# SC_generator.net
KiCad netlist of a schematic drawn in Altium Designer
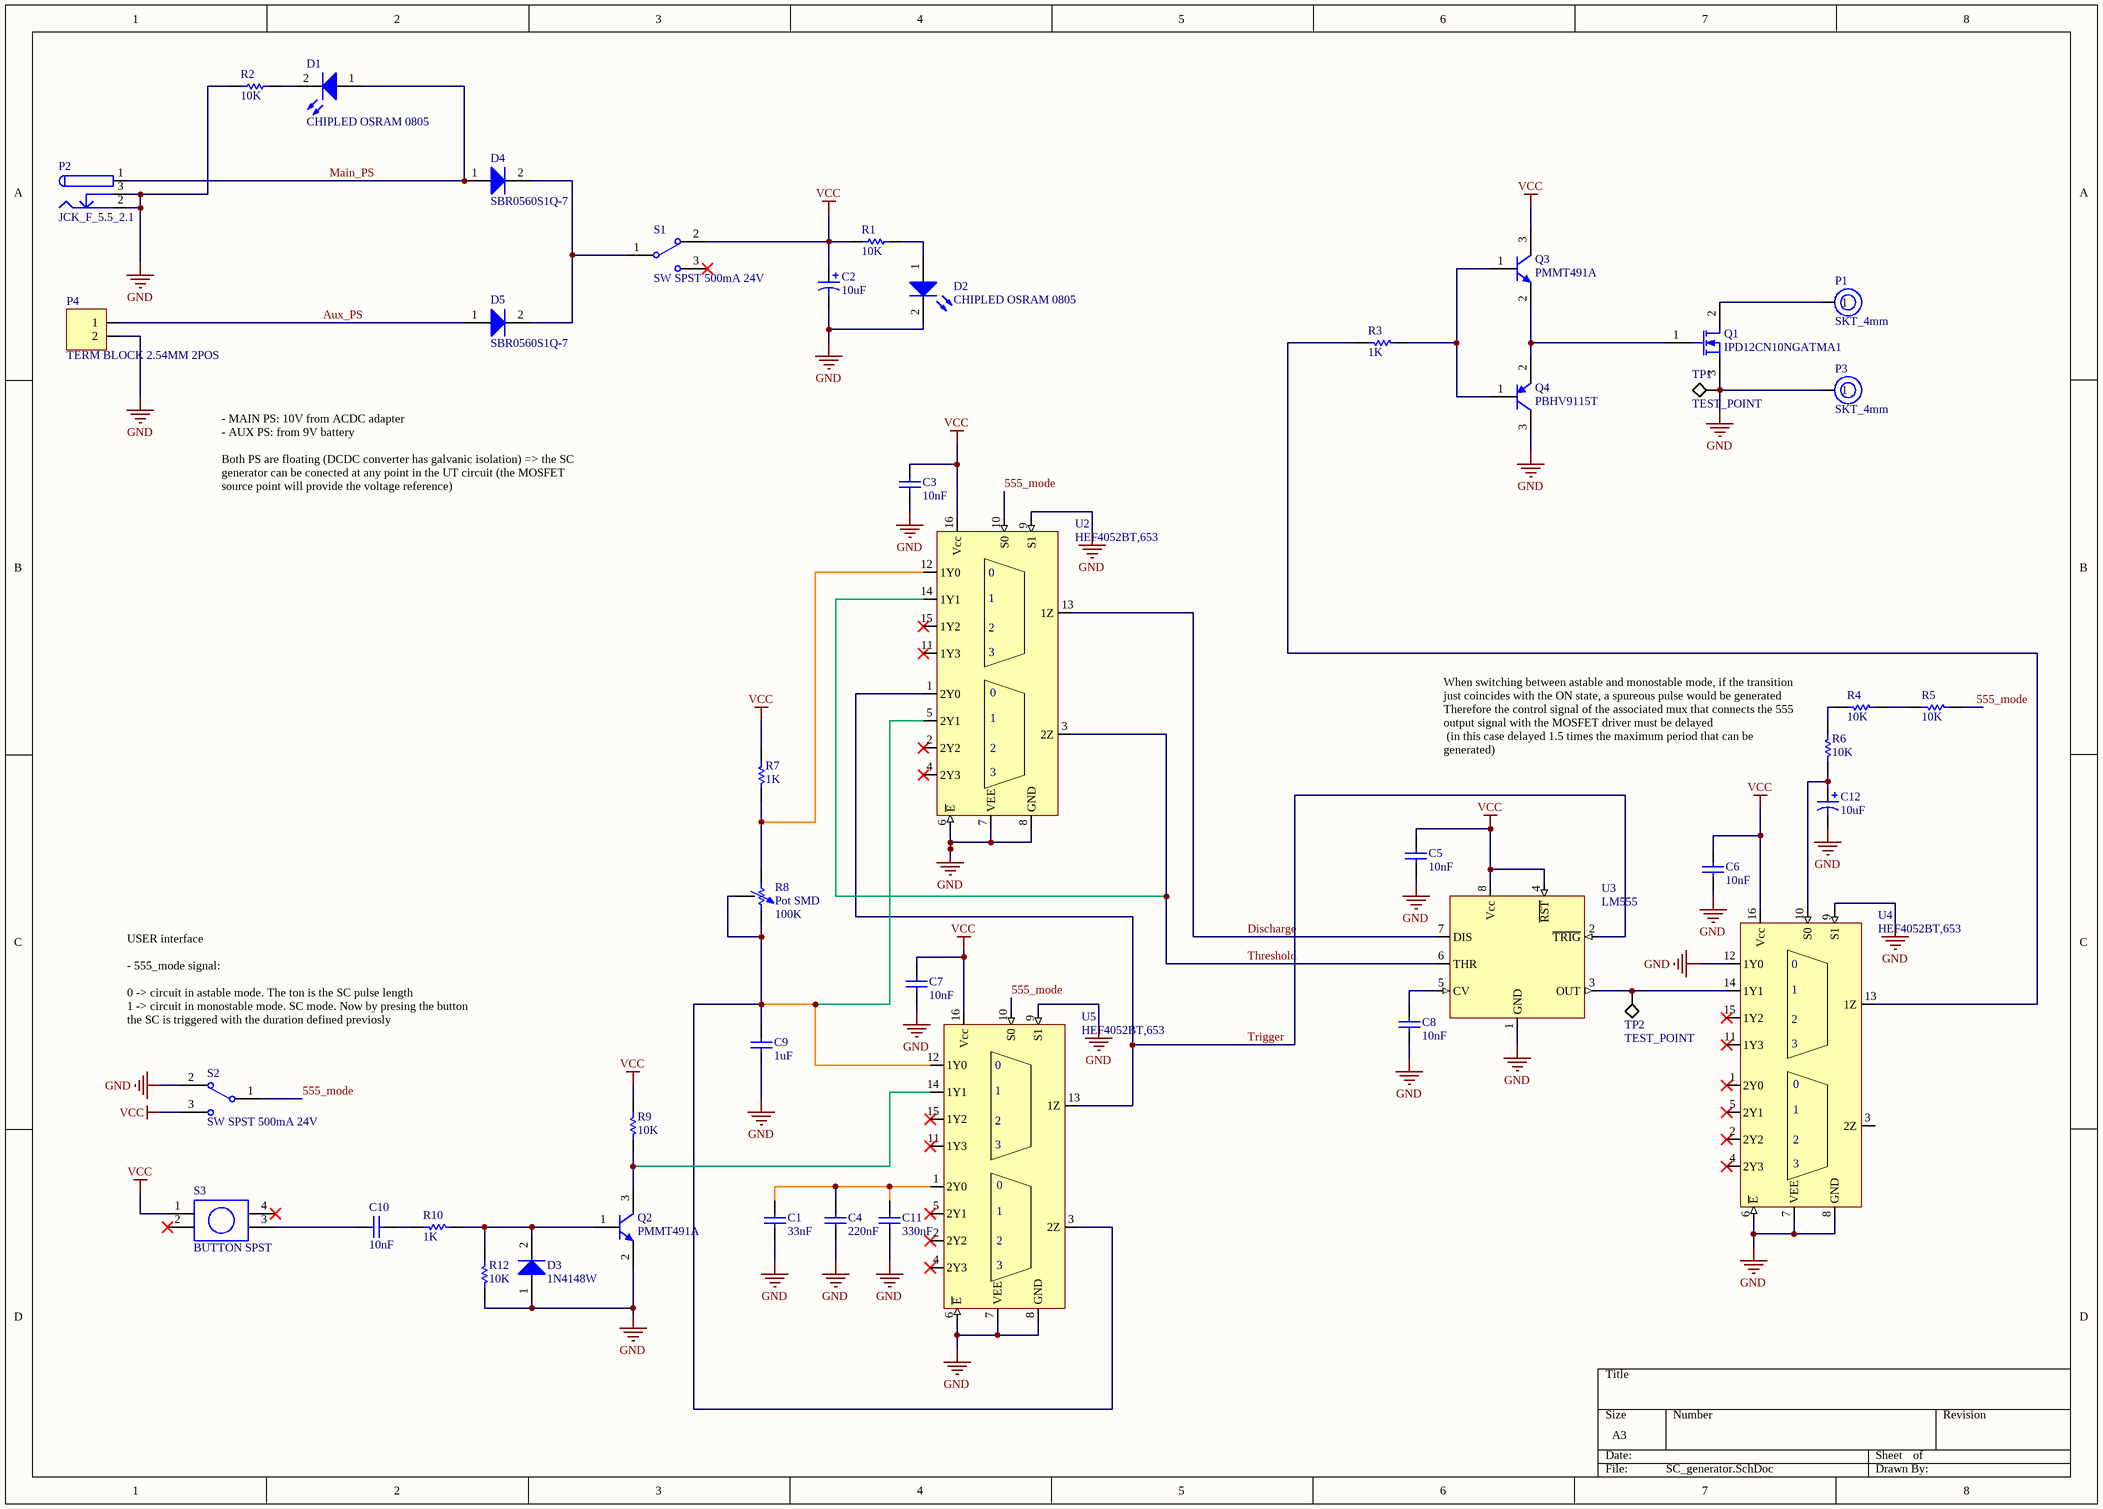
[diagram p0: SC_generator.SchDoc]

(export (version "E")
  (design (tool "Eeschema 10.0.6"))
  (components
    (comp (ref "C1")
      (value "33nF")
      (footprint "CAP_0805_L")
      (description "Generic ceramic capacitor")
      (fields (field (name "Comment") "Cap Semi"))
      (libsource (lib "PAM_capacitors") (part "Cap Semi"))
    )
    (comp (ref "C2")
      (value "10uF")
      (footprint "CAPAE5043X55M")
      (description "Generic electrolitic capacitor")
      (fields (field (name "Comment") "Cap Electrol"))
      (libsource (lib "PAM_capacitors") (part "Cap Electrol"))
    )
    (comp (ref "C3")
      (value "10nF")
      (footprint "CAP_0805_L")
      (description "Generic ceramic capacitor")
      (fields (field (name "Comment") "Cap Semi"))
      (libsource (lib "PAM_capacitors") (part "Cap Semi"))
    )
    (comp (ref "C4")
      (value "220nF")
      (footprint "CAP_0805_L")
      (description "Generic ceramic capacitor")
      (fields (field (name "Comment") "Cap Semi"))
      (libsource (lib "PAM_capacitors") (part "Cap Semi"))
    )
    (comp (ref "C5")
      (value "10nF")
      (footprint "CAP_0805_L")
      (description "Generic ceramic capacitor")
      (fields (field (name "Comment") "Cap Semi"))
      (libsource (lib "PAM_capacitors") (part "Cap Semi"))
    )
    (comp (ref "C6")
      (value "10nF")
      (footprint "CAP_0805_L")
      (description "Generic ceramic capacitor")
      (fields (field (name "Comment") "Cap Semi"))
      (libsource (lib "PAM_capacitors") (part "Cap Semi"))
    )
    (comp (ref "C7")
      (value "10nF")
      (footprint "CAP_0805_L")
      (description "Generic ceramic capacitor")
      (fields (field (name "Comment") "Cap Semi"))
      (libsource (lib "PAM_capacitors") (part "Cap Semi"))
    )
    (comp (ref "C8")
      (value "10nF")
      (footprint "CAP_0805_L")
      (description "Generic ceramic capacitor")
      (fields (field (name "Comment") "Cap Semi"))
      (libsource (lib "PAM_capacitors") (part "Cap Semi"))
    )
    (comp (ref "C9")
      (value "1uF")
      (footprint "CAP_0805_L")
      (description "Generic ceramic capacitor")
      (fields (field (name "Comment") "Cap Semi"))
      (libsource (lib "PAM_capacitors") (part "Cap Semi"))
    )
    (comp (ref "C10")
      (value "10nF")
      (footprint "CAP_0805_L")
      (description "Generic ceramic capacitor")
      (fields (field (name "Comment") "Cap Semi"))
      (libsource (lib "PAM_capacitors") (part "Cap Semi"))
    )
    (comp (ref "C11")
      (value "330nF")
      (footprint "CAP_0805_L")
      (description "Generic ceramic capacitor")
      (fields (field (name "Comment") "Cap Semi"))
      (libsource (lib "PAM_capacitors") (part "Cap Semi"))
    )
    (comp (ref "C12")
      (value "10uF")
      (footprint "CAPAE5043X55M")
      (description "Generic electrolitic capacitor")
      (fields (field (name "Comment") "Cap Electrol"))
      (libsource (lib "PAM_capacitors") (part "Cap Electrol"))
    )
    (comp (ref "D1")
      (value "CHIPLED OSRAM 0805")
      (footprint "CHIPLED_0805_N")
      (libsource (lib "PAM_diodes") (part "CHIPLED 0805"))
    )
    (comp (ref "D2")
      (value "CHIPLED OSRAM 0805")
      (footprint "CHIPLED_0805_N")
      (libsource (lib "PAM_diodes") (part "CHIPLED 0805"))
    )
    (comp (ref "D3")
      (value "1N4148W")
      (footprint "SOD-123_M")
      (description "Diodo de conmutación, 1N4148W-E3-08, 150mA, 75V, SOD-123, 2-Pines, Maximum of 50")
      (libsource (lib "PAM_diodes") (part "1N4148W"))
    )
    (comp (ref "D4")
      (value "SBR0560S1Q-7")
      (footprint "SOD-123_M")
      (description "Diodo Súper barrera Montaje en superficie 60V 500 mA SOD-123")
      (libsource (lib "PAM_diodes") (part "SBR0560S1Q-7"))
    )
    (comp (ref "D5")
      (value "SBR0560S1Q-7")
      (footprint "SOD-123_M")
      (description "Diodo Súper barrera Montaje en superficie 60V 500 mA SOD-123")
      (libsource (lib "PAM_diodes") (part "SBR0560S1Q-7"))
    )
    (comp (ref "P1")
      (value "SKT_4mm")
      (footprint "4MM SAFETY JACK")
      (libsource (lib "PAM_connectors") (part "SKT_4mm"))
    )
    (comp (ref "P2")
      (value "JCK_F_5.5_2.1")
      (footprint "PJ-059A")
      (description "Power Barrel Connector Jack 2.10mm ID (0.083\"), 5.50mm OD (0.217\") Through Hole, Right Angle")
      (libsource (lib "PAM_connectors") (part "jack_female_5.5_2.1"))
    )
    (comp (ref "P3")
      (value "SKT_4mm")
      (footprint "4MM SAFETY JACK")
      (libsource (lib "PAM_connectors") (part "SKT_4mm"))
    )
    (comp (ref "P4")
      (value "TERM BLOCK 2.54MM 2POS")
      (footprint "TERM BLOCK 2.54MM 2POS")
      (description "2 Position Wire to Board Terminal Block Horizontal with Board 0.100\" (2.54mm) Through Hole")
      (libsource (lib "PAM_connectors") (part "TERM BLOCK 2.54MM 2POS"))
    )
    (comp (ref "Q1")
      (value "IPD12CN10NGATMA1")
      (footprint "TO-252/DPAK")
      (description "Canal N Montaje en superficie 100V 67 A (Tc) 125 W (Tc) PG-TO252-3")
      (libsource (lib "PAM_Transistors") (part "IPD12CN10NGATMA1"))
    )
    (comp (ref "Q2")
      (value "PMMT491A")
      (footprint "SOT-23")
      (description "Transistor de Unión Bipolar Único, NPN, 40 V, 250 mW, 1 A, 300 hFE")
      (libsource (lib "PAM_Transistors") (part "PMMT491A"))
    )
    (comp (ref "Q3")
      (value "PMMT491A")
      (footprint "SOT-23")
      (description "Transistor de Unión Bipolar Único, NPN, 40 V, 250 mW, 1 A, 300 hFE")
      (libsource (lib "PAM_Transistors") (part "PMMT491A"))
    )
    (comp (ref "Q4")
      (value "PBHV9115T")
      (footprint "SOT-23")
      (description "Transistor de Unión Bipolar Único, PNP, -150 V, 115 MHz, 300 mW, -1 A, 220 hFE")
      (libsource (lib "PAM_Transistors") (part "PBHV9115T"))
    )
    (comp (ref "R1")
      (value "10K")
      (footprint "RES_1206_N")
      (description "Generic resistor")
      (fields (field (name "Comment") "Res semi"))
      (libsource (lib "PAM_resistors") (part "Res semi"))
    )
    (comp (ref "R2")
      (value "10K")
      (footprint "RES_1206_N")
      (description "Generic resistor")
      (fields (field (name "Comment") "Res semi"))
      (libsource (lib "PAM_resistors") (part "Res semi"))
    )
    (comp (ref "R3")
      (value "1K")
      (footprint "RES_1206_N")
      (description "Generic resistor")
      (fields (field (name "Comment") "Res semi"))
      (libsource (lib "PAM_resistors") (part "Res semi"))
    )
    (comp (ref "R4")
      (value "10K")
      (footprint "RES_1206_N")
      (description "Generic resistor")
      (fields (field (name "Comment") "Res semi"))
      (libsource (lib "PAM_resistors") (part "Res semi"))
    )
    (comp (ref "R5")
      (value "10K")
      (footprint "RES_1206_N")
      (description "Generic resistor")
      (fields (field (name "Comment") "Res semi"))
      (libsource (lib "PAM_resistors") (part "Res semi"))
    )
    (comp (ref "R6")
      (value "10K")
      (footprint "RES_1206_N")
      (description "Generic resistor")
      (fields (field (name "Comment") "Res semi"))
      (libsource (lib "PAM_resistors") (part "Res semi"))
    )
    (comp (ref "R7")
      (value "1K")
      (footprint "RES_1206_N")
      (description "Generic resistor")
      (fields (field (name "Comment") "Res semi"))
      (libsource (lib "PAM_resistors") (part "Res semi"))
    )
    (comp (ref "R8")
      (value "Pot SMD")
      (footprint "3361P_POT")
      (description "Generic pot SMD")
      (fields (field (name "ALTIUM_VALUE") "100K"))
      (libsource (lib "PAM_resistors") (part "Pot SMD"))
    )
    (comp (ref "R9")
      (value "10K")
      (footprint "RES_1206_N")
      (description "Generic resistor")
      (fields (field (name "Comment") "Res semi"))
      (libsource (lib "PAM_resistors") (part "Res semi"))
    )
    (comp (ref "R10")
      (value "1K")
      (footprint "RES_1206_N")
      (description "Generic resistor")
      (fields (field (name "Comment") "Res semi"))
      (libsource (lib "PAM_resistors") (part "Res semi"))
    )
    (comp (ref "R12")
      (value "10K")
      (footprint "RES_1206_N")
      (description "Generic resistor")
      (fields (field (name "Comment") "Res semi"))
      (libsource (lib "PAM_resistors") (part "Res semi"))
    )
    (comp (ref "S1")
      (value "SW SPST 500mA 24V")
      (footprint "DIP_3x1_slide_switch")
      (description "Interruptor SIP, SPST, Pasante, Actuador Deslizante, 500 mA a 24 V")
      (libsource (lib "PAM_switches_buttons") (part "SW SPST TH"))
    )
    (comp (ref "S2")
      (value "SW SPST 500mA 24V")
      (footprint "DIP_3x1_slide_switch")
      (description "Interruptor SIP, SPST, Pasante, Actuador Deslizante, 500 mA a 24 V")
      (libsource (lib "PAM_switches_buttons") (part "SW SPST TH"))
    )
    (comp (ref "S3")
      (value "BUTTON SPST")
      (footprint "BUTTON SPDT")
      (description "Interruptor táctil tipo Botón, Negro, contactos SPST-NA, Montaje superficial")
      (libsource (lib "PAM_switches_buttons") (part "BUTTON SPST"))
    )
    (comp (ref "TP1")
      (value "TEST_POINT")
      (footprint "TP_SMD_pin")
      (description "Generic test point, several footprints")
      (libsource (lib "PAM_connectors") (part "TEST_POINT"))
    )
    (comp (ref "TP2")
      (value "TEST_POINT")
      (footprint "TP_SMD")
      (description "Generic test point, several footprints")
      (libsource (lib "PAM_connectors") (part "TEST_POINT"))
    )
    (comp (ref "U2")
      (value "HEF4052BT,653")
      (footprint "SO16_M")
      (description "IC MUX/DEMUX DUAL 4X1 16SOIC")
      (fields (field (name "MFR") "Nexperia"))
      (libsource (lib "PAM_ICs") (part "HEF4052BT,653"))
    )
    (comp (ref "U3")
      (value "LM555")
      (footprint "SO-8_M")
      (description "IC OSC SINGLE TIMER")
      (libsource (lib "PAM_ICs") (part "LM555"))
    )
    (comp (ref "U4")
      (value "HEF4052BT,653")
      (footprint "SO16_M")
      (description "IC MUX/DEMUX DUAL 4X1 16SOIC")
      (fields (field (name "MFR") "Nexperia"))
      (libsource (lib "PAM_ICs") (part "HEF4052BT,653"))
    )
    (comp (ref "U5")
      (value "HEF4052BT,653")
      (footprint "SO16_M")
      (description "IC MUX/DEMUX DUAL 4X1 16SOIC")
      (fields (field (name "MFR") "Nexperia"))
      (libsource (lib "PAM_ICs") (part "HEF4052BT,653"))
    )
  )
  (nets
    (net (code "1") (name "/555_mode") (class "Default")
      (node (ref "R5") (pin "1") (pinfunction "1_1") (pintype "passive"))
      (node (ref "S2") (pin "1") (pinfunction "C_1") (pintype "passive"))
      (node (ref "U2") (pin "10") (pinfunction "S0_10") (pintype "input"))
      (node (ref "U5") (pin "10") (pinfunction "S0_10") (pintype "input"))
    )
    (net (code "2") (name "/Aux_PS") (class "Default")
      (node (ref "D5") (pin "1") (pinfunction "A_1") (pintype "passive"))
      (node (ref "P4") (pin "1") (pinfunction "1_1") (pintype "passive"))
    )
    (net (code "3") (name "/Discharge") (class "Default")
      (node (ref "U2") (pin "13") (pinfunction "1Z_13") (pintype "bidirectional"))
      (node (ref "U3") (pin "7") (pinfunction "DIS_7") (pintype "passive"))
    )
    (net (code "4") (name "/Main_PS") (class "Default")
      (node (ref "D1") (pin "1") (pinfunction "A_1") (pintype "passive"))
      (node (ref "D4") (pin "1") (pinfunction "A_1") (pintype "passive"))
      (node (ref "P2") (pin "1") (pinfunction "tip_1") (pintype "power_in"))
    )
    (net (code "5") (name "/Threshold") (class "Default")
      (node (ref "U2") (pin "14") (pinfunction "1Y1_14") (pintype "bidirectional"))
      (node (ref "U2") (pin "3") (pinfunction "2Z_3") (pintype "bidirectional"))
      (node (ref "U3") (pin "6") (pinfunction "THR_6") (pintype "passive"))
    )
    (net (code "6") (name "/Trigger") (class "Default")
      (node (ref "U2") (pin "1") (pinfunction "2Y0_1") (pintype "bidirectional"))
      (node (ref "U3") (pin "2") (pinfunction "~{TRIG}_2") (pintype "input"))
      (node (ref "U5") (pin "13") (pinfunction "1Z_13") (pintype "bidirectional"))
    )
    (net (code "7") (name "GND") (class "Default")
      (node (ref "C1") (pin "1") (pinfunction "1_1") (pintype "passive"))
      (node (ref "C11") (pin "1") (pinfunction "1_1") (pintype "passive"))
      (node (ref "C12") (pin "2") (pinfunction "2_2") (pintype "passive"))
      (node (ref "C2") (pin "2") (pinfunction "2_2") (pintype "passive"))
      (node (ref "C3") (pin "1") (pinfunction "1_1") (pintype "passive"))
      (node (ref "C4") (pin "1") (pinfunction "1_1") (pintype "passive"))
      (node (ref "C5") (pin "1") (pinfunction "1_1") (pintype "passive"))
      (node (ref "C6") (pin "1") (pinfunction "1_1") (pintype "passive"))
      (node (ref "C7") (pin "1") (pinfunction "1_1") (pintype "passive"))
      (node (ref "C8") (pin "1") (pinfunction "1_1") (pintype "passive"))
      (node (ref "C9") (pin "1") (pinfunction "1_1") (pintype "passive"))
      (node (ref "D2") (pin "2") (pinfunction "K_2") (pintype "passive"))
      (node (ref "D3") (pin "1") (pinfunction "A_1") (pintype "passive"))
      (node (ref "P2") (pin "2") (pinfunction "sleeve_2") (pintype "power_in"))
      (node (ref "P2") (pin "3") (pinfunction "connector_detec_3") (pintype "power_in"))
      (node (ref "P3") (pin "1") (pinfunction "1_1") (pintype "passive"))
      (node (ref "P4") (pin "2") (pinfunction "2_2") (pintype "passive"))
      (node (ref "Q1") (pin "3") (pinfunction "S_3") (pintype "passive"))
      (node (ref "Q2") (pin "2") (pinfunction "E_2") (pintype "passive"))
      (node (ref "Q4") (pin "3") (pinfunction "C_3") (pintype "passive"))
      (node (ref "R12") (pin "1") (pinfunction "1_1") (pintype "passive"))
      (node (ref "R2") (pin "1") (pinfunction "1_1") (pintype "passive"))
      (node (ref "S2") (pin "2") (pinfunction "2_2") (pintype "passive"))
      (node (ref "TP1") (pin "1") (pinfunction "1_1") (pintype "passive"))
      (node (ref "U2") (pin "6") (pinfunction "~{E}_6") (pintype "input"))
      (node (ref "U2") (pin "7") (pinfunction "VEE_7") (pintype "power_in"))
      (node (ref "U2") (pin "8") (pinfunction "GND_8") (pintype "power_in"))
      (node (ref "U2") (pin "9") (pinfunction "S1_9") (pintype "input"))
      (node (ref "U3") (pin "1") (pinfunction "GND_1") (pintype "power_in"))
      (node (ref "U4") (pin "12") (pinfunction "1Y0_12") (pintype "bidirectional"))
      (node (ref "U4") (pin "6") (pinfunction "~{E}_6") (pintype "input"))
      (node (ref "U4") (pin "7") (pinfunction "VEE_7") (pintype "power_in"))
      (node (ref "U4") (pin "8") (pinfunction "GND_8") (pintype "power_in"))
      (node (ref "U4") (pin "9") (pinfunction "S1_9") (pintype "input"))
      (node (ref "U5") (pin "6") (pinfunction "~{E}_6") (pintype "input"))
      (node (ref "U5") (pin "7") (pinfunction "VEE_7") (pintype "power_in"))
      (node (ref "U5") (pin "8") (pinfunction "GND_8") (pintype "power_in"))
      (node (ref "U5") (pin "9") (pinfunction "S1_9") (pintype "input"))
    )
    (net (code "8") (name "Net-(C10-Pad2)") (class "Default")
      (node (ref "C10") (pin "2") (pinfunction "2_2") (pintype "passive"))
      (node (ref "R10") (pin "2") (pinfunction "2_2") (pintype "passive"))
    )
    (net (code "9") (name "Net-(D1-K)") (class "Default")
      (node (ref "D1") (pin "2") (pinfunction "K_2") (pintype "passive"))
      (node (ref "R2") (pin "2") (pinfunction "2_2") (pintype "passive"))
    )
    (net (code "10") (name "Net-(D2-A)") (class "Default")
      (node (ref "D2") (pin "1") (pinfunction "A_1") (pintype "passive"))
      (node (ref "R1") (pin "1") (pinfunction "1_1") (pintype "passive"))
    )
    (net (code "11") (name "Net-(D3-K)") (class "Default")
      (node (ref "D3") (pin "2") (pinfunction "K_2") (pintype "passive"))
      (node (ref "Q2") (pin "1") (pinfunction "B_1") (pintype "passive"))
      (node (ref "R10") (pin "1") (pinfunction "1_1") (pintype "passive"))
      (node (ref "R12") (pin "2") (pinfunction "2_2") (pintype "passive"))
    )
    (net (code "12") (name "Net-(D4-K)") (class "Default")
      (node (ref "D4") (pin "2") (pinfunction "K_2") (pintype "passive"))
      (node (ref "D5") (pin "2") (pinfunction "K_2") (pintype "passive"))
      (node (ref "S1") (pin "1") (pinfunction "C_1") (pintype "passive"))
    )
    (net (code "13") (name "Net-(Q1-D)") (class "Default")
      (node (ref "P1") (pin "1") (pinfunction "1_1") (pintype "passive"))
      (node (ref "Q1") (pin "2") (pinfunction "D_2") (pintype "passive"))
    )
    (net (code "14") (name "Net-(Q1-G)") (class "Default")
      (node (ref "Q1") (pin "1") (pinfunction "G_1") (pintype "passive"))
      (node (ref "Q3") (pin "2") (pinfunction "E_2") (pintype "passive"))
      (node (ref "Q4") (pin "2") (pinfunction "E_2") (pintype "passive"))
    )
    (net (code "15") (name "Net-(Q2-C)") (class "Default")
      (node (ref "Q2") (pin "3") (pinfunction "C_3") (pintype "passive"))
      (node (ref "R9") (pin "1") (pinfunction "1_1") (pintype "passive"))
      (node (ref "U5") (pin "14") (pinfunction "1Y1_14") (pintype "bidirectional"))
    )
    (net (code "16") (name "Net-(Q3-B)") (class "Default")
      (node (ref "Q3") (pin "1") (pinfunction "B_1") (pintype "passive"))
      (node (ref "Q4") (pin "1") (pinfunction "B_1") (pintype "passive"))
      (node (ref "R3") (pin "1") (pinfunction "1_1") (pintype "passive"))
    )
    (net (code "17") (name "Net-(R4-Pad1)") (class "Default")
      (node (ref "R4") (pin "1") (pinfunction "1_1") (pintype "passive"))
      (node (ref "R5") (pin "2") (pinfunction "2_2") (pintype "passive"))
    )
    (net (code "18") (name "Net-(R4-Pad2)") (class "Default")
      (node (ref "R4") (pin "2") (pinfunction "2_2") (pintype "passive"))
      (node (ref "R6") (pin "2") (pinfunction "2_2") (pintype "passive"))
    )
    (net (code "19") (name "Net-(S3-B2)") (class "Default")
      (node (ref "C10") (pin "1") (pinfunction "1_1") (pintype "passive"))
      (node (ref "S3") (pin "3") (pinfunction "B2_3") (pintype "passive"))
    )
    (net (code "20") (name "Net-(U2-1Y0)") (class "Default")
      (node (ref "R7") (pin "1") (pinfunction "1_1") (pintype "passive"))
      (node (ref "R8") (pin "1") (pinfunction "1_1") (pintype "passive"))
      (node (ref "U2") (pin "12") (pinfunction "1Y0_12") (pintype "bidirectional"))
    )
    (net (code "21") (name "Net-(U2-2Y1)") (class "Default")
      (node (ref "C9") (pin "2") (pinfunction "2_2") (pintype "passive"))
      (node (ref "R8") (pin "2") (pinfunction "2_2") (pintype "passive"))
      (node (ref "R8") (pin "3") (pinfunction "3_3") (pintype "passive"))
      (node (ref "U2") (pin "5") (pinfunction "2Y1_5") (pintype "bidirectional"))
      (node (ref "U5") (pin "12") (pinfunction "1Y0_12") (pintype "bidirectional"))
      (node (ref "U5") (pin "3") (pinfunction "2Z_3") (pintype "bidirectional"))
    )
    (net (code "22") (name "Net-(U3-CV)") (class "Default")
      (node (ref "C8") (pin "2") (pinfunction "2_2") (pintype "passive"))
      (node (ref "U3") (pin "5") (pinfunction "CV_5") (pintype "input"))
    )
    (net (code "23") (name "Net-(U3-OUT)") (class "Default")
      (node (ref "TP2") (pin "1") (pinfunction "1_1") (pintype "passive"))
      (node (ref "U3") (pin "3") (pinfunction "OUT_3") (pintype "output"))
      (node (ref "U4") (pin "14") (pinfunction "1Y1_14") (pintype "bidirectional"))
    )
    (net (code "24") (name "Net-(U4-1Z)") (class "Default")
      (node (ref "R3") (pin "2") (pinfunction "2_2") (pintype "passive"))
      (node (ref "U4") (pin "13") (pinfunction "1Z_13") (pintype "bidirectional"))
    )
    (net (code "25") (name "Net-(U4-S0)") (class "Default")
      (node (ref "C12") (pin "1") (pinfunction "1_1") (pintype "passive"))
      (node (ref "R6") (pin "1") (pinfunction "1_1") (pintype "passive"))
      (node (ref "U4") (pin "10") (pinfunction "S0_10") (pintype "input"))
    )
    (net (code "26") (name "Net-(U5-2Y0)") (class "Default")
      (node (ref "C1") (pin "2") (pinfunction "2_2") (pintype "passive"))
      (node (ref "C11") (pin "2") (pinfunction "2_2") (pintype "passive"))
      (node (ref "C4") (pin "2") (pinfunction "2_2") (pintype "passive"))
      (node (ref "U5") (pin "1") (pinfunction "2Y0_1") (pintype "bidirectional"))
    )
    (net (code "27") (name "VCC") (class "Default")
      (node (ref "C2") (pin "1") (pinfunction "1_1") (pintype "passive"))
      (node (ref "C3") (pin "2") (pinfunction "2_2") (pintype "passive"))
      (node (ref "C5") (pin "2") (pinfunction "2_2") (pintype "passive"))
      (node (ref "C6") (pin "2") (pinfunction "2_2") (pintype "passive"))
      (node (ref "C7") (pin "2") (pinfunction "2_2") (pintype "passive"))
      (node (ref "Q3") (pin "3") (pinfunction "C_3") (pintype "passive"))
      (node (ref "R1") (pin "2") (pinfunction "2_2") (pintype "passive"))
      (node (ref "R7") (pin "2") (pinfunction "2_2") (pintype "passive"))
      (node (ref "R9") (pin "2") (pinfunction "2_2") (pintype "passive"))
      (node (ref "S1") (pin "2") (pinfunction "2_2") (pintype "passive"))
      (node (ref "S2") (pin "3") (pinfunction "3_3") (pintype "passive"))
      (node (ref "S3") (pin "1") (pinfunction "A1_1") (pintype "passive"))
      (node (ref "U2") (pin "16") (pinfunction "Vcc_16") (pintype "power_in"))
      (node (ref "U3") (pin "4") (pinfunction "~{RST}_4") (pintype "input"))
      (node (ref "U3") (pin "8") (pinfunction "Vcc_8") (pintype "power_in"))
      (node (ref "U4") (pin "16") (pinfunction "Vcc_16") (pintype "power_in"))
      (node (ref "U5") (pin "16") (pinfunction "Vcc_16") (pintype "power_in"))
    )
    (net (code "28") (name "unconnected-(S1-Pad3)") (class "Default")
      (node (ref "S1") (pin "3") (pinfunction "3_3") (pintype "passive+no_connect"))
    )
    (net (code "29") (name "unconnected-(S3-A2-Pad2)") (class "Default")
      (node (ref "S3") (pin "2") (pinfunction "A2_2") (pintype "passive+no_connect"))
    )
    (net (code "30") (name "unconnected-(S3-B1-Pad4)") (class "Default")
      (node (ref "S3") (pin "4") (pinfunction "B1_4") (pintype "passive+no_connect"))
    )
    (net (code "31") (name "unconnected-(U2-1Y2-Pad15)") (class "Default")
      (node (ref "U2") (pin "15") (pinfunction "1Y2_15") (pintype "bidirectional+no_connect"))
    )
    (net (code "32") (name "unconnected-(U2-1Y3-Pad11)") (class "Default")
      (node (ref "U2") (pin "11") (pinfunction "1Y3_11") (pintype "bidirectional+no_connect"))
    )
    (net (code "33") (name "unconnected-(U2-2Y2-Pad2)") (class "Default")
      (node (ref "U2") (pin "2") (pinfunction "2Y2_2") (pintype "bidirectional+no_connect"))
    )
    (net (code "34") (name "unconnected-(U2-2Y3-Pad4)") (class "Default")
      (node (ref "U2") (pin "4") (pinfunction "2Y3_4") (pintype "bidirectional+no_connect"))
    )
    (net (code "35") (name "unconnected-(U4-1Y2-Pad15)") (class "Default")
      (node (ref "U4") (pin "15") (pinfunction "1Y2_15") (pintype "bidirectional+no_connect"))
    )
    (net (code "36") (name "unconnected-(U4-1Y3-Pad11)") (class "Default")
      (node (ref "U4") (pin "11") (pinfunction "1Y3_11") (pintype "bidirectional+no_connect"))
    )
    (net (code "37") (name "unconnected-(U4-2Y0-Pad1)") (class "Default")
      (node (ref "U4") (pin "1") (pinfunction "2Y0_1") (pintype "bidirectional+no_connect"))
    )
    (net (code "38") (name "unconnected-(U4-2Y1-Pad5)") (class "Default")
      (node (ref "U4") (pin "5") (pinfunction "2Y1_5") (pintype "bidirectional+no_connect"))
    )
    (net (code "39") (name "unconnected-(U4-2Y2-Pad2)") (class "Default")
      (node (ref "U4") (pin "2") (pinfunction "2Y2_2") (pintype "bidirectional+no_connect"))
    )
    (net (code "40") (name "unconnected-(U4-2Y3-Pad4)") (class "Default")
      (node (ref "U4") (pin "4") (pinfunction "2Y3_4") (pintype "bidirectional+no_connect"))
    )
    (net (code "41") (name "unconnected-(U4-2Z-Pad3)") (class "Default")
      (node (ref "U4") (pin "3") (pinfunction "2Z_3") (pintype "bidirectional"))
    )
    (net (code "42") (name "unconnected-(U5-1Y2-Pad15)") (class "Default")
      (node (ref "U5") (pin "15") (pinfunction "1Y2_15") (pintype "bidirectional+no_connect"))
    )
    (net (code "43") (name "unconnected-(U5-1Y3-Pad11)") (class "Default")
      (node (ref "U5") (pin "11") (pinfunction "1Y3_11") (pintype "bidirectional+no_connect"))
    )
    (net (code "44") (name "unconnected-(U5-2Y1-Pad5)") (class "Default")
      (node (ref "U5") (pin "5") (pinfunction "2Y1_5") (pintype "bidirectional+no_connect"))
    )
    (net (code "45") (name "unconnected-(U5-2Y2-Pad2)") (class "Default")
      (node (ref "U5") (pin "2") (pinfunction "2Y2_2") (pintype "bidirectional+no_connect"))
    )
    (net (code "46") (name "unconnected-(U5-2Y3-Pad4)") (class "Default")
      (node (ref "U5") (pin "4") (pinfunction "2Y3_4") (pintype "bidirectional+no_connect"))
    )
  )
)
